# TopLevel.net
KiCad netlist of a schematic drawn in Altium Designer
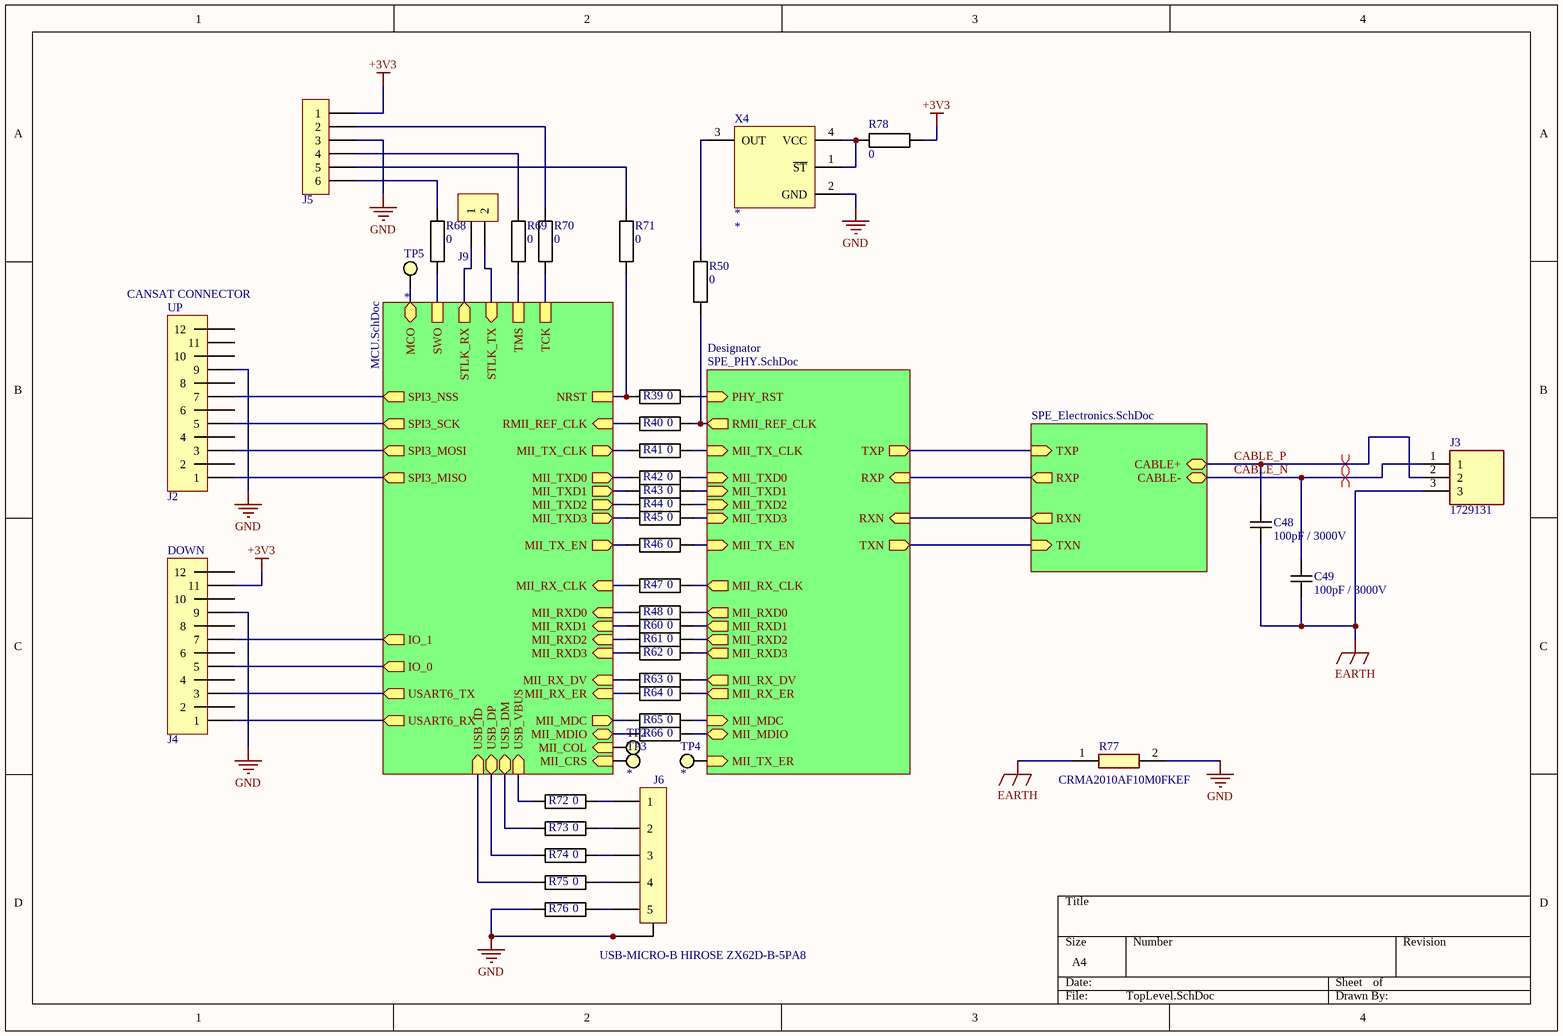
[diagram p0: TopLevel.SchDoc]

(export (version "E")
  (design (tool "Eeschema 10.0.6"))
  (components
    (comp (ref "C48")
      (value "100pF / 3000V")
      (footprint "CAPACITOR 4520 REFLOW")
      (description "Capacitor")
      (libsource (lib "Capacitor") (part "Capacitor"))
    )
    (comp (ref "C49")
      (value "100pF / 3000V")
      (footprint "CAPACITOR 4520 REFLOW")
      (description "Capacitor")
      (libsource (lib "Capacitor") (part "Capacitor"))
    )
    (comp (ref "J2")
      (value "*")
      (footprint "PINHEADER2X6 P2.54 SIDE MOUNT")
      (description "Plug connector")
      (libsource (lib "PinHeader") (part "PinHeader2x6"))
    )
    (comp (ref "J3")
      (value "1729131")
      (footprint "1729131")
      (description "Connector")
      (fields (field (name "MOUSER PART NUMBER") "651-1729131"))
      (libsource (lib "*") (part "1729131"))
    )
    (comp (ref "J4")
      (value "*")
      (footprint "PINHEADER2X6 P2.54 SIDE MOUNT")
      (description "Plug connector")
      (libsource (lib "PinHeader") (part "PinHeader2x6"))
    )
    (comp (ref "J5")
      (value "*")
      (footprint "PinHeader1x6 P2.54")
      (description "Plug connector")
      (libsource (lib "PinHeader") (part "PinHeader1x6"))
    )
    (comp (ref "J6")
      (value "USB-MICRO-B HIROSE ZX62D-B-5PA8")
      (footprint "USB-MICRO-B HIROSE ZX62D-B-5PA8")
      (libsource (lib "Connector") (part "USB-MICRO-B HIROSE ZX62D-B-5PA8"))
    )
    (comp (ref "J9")
      (value "*")
      (footprint "PinHeader1x2 P2.54")
      (description "Plug connector")
      (libsource (lib "PinHeader") (part "PinHeader1x2"))
    )
    (comp (ref "R39")
      (value "0")
      (footprint "RESISTOR 1608 REFLOW")
      (description "Resistor")
      (libsource (lib "Resistor") (part "Resistor"))
    )
    (comp (ref "R40")
      (value "0")
      (footprint "RESISTOR 1608 REFLOW")
      (description "Resistor")
      (libsource (lib "Resistor") (part "Resistor"))
    )
    (comp (ref "R41")
      (value "0")
      (footprint "RESISTOR 1608 REFLOW")
      (description "Resistor")
      (libsource (lib "Resistor") (part "Resistor"))
    )
    (comp (ref "R42")
      (value "0")
      (footprint "RESISTOR 1608 REFLOW")
      (description "Resistor")
      (libsource (lib "Resistor") (part "Resistor"))
    )
    (comp (ref "R43")
      (value "0")
      (footprint "RESISTOR 1608 REFLOW")
      (description "Resistor")
      (libsource (lib "Resistor") (part "Resistor"))
    )
    (comp (ref "R44")
      (value "0")
      (footprint "RESISTOR 1608 REFLOW")
      (description "Resistor")
      (libsource (lib "Resistor") (part "Resistor"))
    )
    (comp (ref "R45")
      (value "0")
      (footprint "RESISTOR 1608 REFLOW")
      (description "Resistor")
      (libsource (lib "Resistor") (part "Resistor"))
    )
    (comp (ref "R46")
      (value "0")
      (footprint "RESISTOR 1608 REFLOW")
      (description "Resistor")
      (libsource (lib "Resistor") (part "Resistor"))
    )
    (comp (ref "R47")
      (value "0")
      (footprint "RESISTOR 1608 REFLOW")
      (description "Resistor")
      (libsource (lib "Resistor") (part "Resistor"))
    )
    (comp (ref "R48")
      (value "0")
      (footprint "RESISTOR 1608 REFLOW")
      (description "Resistor")
      (libsource (lib "Resistor") (part "Resistor"))
    )
    (comp (ref "R50")
      (value "0")
      (footprint "RESISTOR 1608 REFLOW")
      (description "Resistor")
      (libsource (lib "Resistor") (part "Resistor"))
    )
    (comp (ref "R60")
      (value "0")
      (footprint "RESISTOR 1608 REFLOW")
      (description "Resistor")
      (libsource (lib "Resistor") (part "Resistor"))
    )
    (comp (ref "R61")
      (value "0")
      (footprint "RESISTOR 1608 REFLOW")
      (description "Resistor")
      (libsource (lib "Resistor") (part "Resistor"))
    )
    (comp (ref "R62")
      (value "0")
      (footprint "RESISTOR 1608 REFLOW")
      (description "Resistor")
      (libsource (lib "Resistor") (part "Resistor"))
    )
    (comp (ref "R63")
      (value "0")
      (footprint "RESISTOR 1608 REFLOW")
      (description "Resistor")
      (libsource (lib "Resistor") (part "Resistor"))
    )
    (comp (ref "R64")
      (value "0")
      (footprint "RESISTOR 1608 REFLOW")
      (description "Resistor")
      (libsource (lib "Resistor") (part "Resistor"))
    )
    (comp (ref "R65")
      (value "0")
      (footprint "RESISTOR 1608 REFLOW")
      (description "Resistor")
      (libsource (lib "Resistor") (part "Resistor"))
    )
    (comp (ref "R66")
      (value "0")
      (footprint "RESISTOR 1608 REFLOW")
      (description "Resistor")
      (libsource (lib "Resistor") (part "Resistor"))
    )
    (comp (ref "R68")
      (value "0")
      (footprint "RESISTOR 1608 REFLOW")
      (description "Resistor")
      (libsource (lib "Resistor") (part "Resistor"))
    )
    (comp (ref "R69")
      (value "0")
      (footprint "RESISTOR 1608 REFLOW")
      (description "Resistor")
      (libsource (lib "Resistor") (part "Resistor"))
    )
    (comp (ref "R70")
      (value "0")
      (footprint "RESISTOR 1608 REFLOW")
      (description "Resistor")
      (libsource (lib "Resistor") (part "Resistor"))
    )
    (comp (ref "R71")
      (value "0")
      (footprint "RESISTOR 1608 REFLOW")
      (description "Resistor")
      (libsource (lib "Resistor") (part "Resistor"))
    )
    (comp (ref "R72")
      (value "0")
      (footprint "RESISTOR 1005 REFLOW")
      (description "Resistor")
      (libsource (lib "Resistor") (part "Resistor"))
    )
    (comp (ref "R73")
      (value "0")
      (footprint "RESISTOR 1005 REFLOW")
      (description "Resistor")
      (libsource (lib "Resistor") (part "Resistor"))
    )
    (comp (ref "R74")
      (value "0")
      (footprint "RESISTOR 1005 REFLOW")
      (description "Resistor")
      (libsource (lib "Resistor") (part "Resistor"))
    )
    (comp (ref "R75")
      (value "0")
      (footprint "RESISTOR 1005 REFLOW")
      (description "Resistor")
      (libsource (lib "Resistor") (part "Resistor"))
    )
    (comp (ref "R76")
      (value "0")
      (footprint "RESISTOR 1005 REFLOW")
      (description "Resistor")
      (libsource (lib "Resistor") (part "Resistor"))
    )
    (comp (ref "R77")
      (value "CRMA2010AF10M0FKEF")
      (footprint "RESC5125X74N")
      (description "Resistor")
      (fields
        (field (name "MANUFACTURER_PART_NUMBER") "CRMA2010AF1K00FKEF")
        (field (name "MOUSER PART NUMBER") "71-CRMA2010AF1K00FKF")
      )
      (libsource (lib "*") (part "CRMA2010AF1K00FKEF"))
    )
    (comp (ref "R78")
      (value "0")
      (footprint "RESISTOR 1608 REFLOW")
      (description "Resistor")
      (libsource (lib "Resistor") (part "Resistor"))
    )
    (comp (ref "TP2")
      (value "*")
      (footprint "Pad D0.8")
      (description "Pad")
      (libsource (lib "Testpoint") (part "Pad"))
    )
    (comp (ref "TP3")
      (value "*")
      (footprint "Pad D0.8")
      (description "Pad")
      (libsource (lib "Testpoint") (part "Pad"))
    )
    (comp (ref "TP4")
      (value "*")
      (footprint "Pad D0.8")
      (description "Pad")
      (libsource (lib "Testpoint") (part "Pad"))
    )
    (comp (ref "TP5")
      (value "*")
      (footprint "Pad D0.8")
      (description "Pad")
      (libsource (lib "Testpoint") (part "Pad"))
    )
    (comp (ref "X4")
      (value "*")
      (footprint "Oscillator C2.5x2 Seiko Epson SPXO SG-210STF")
      (description "Oscillator C2.5x2 Seiko Epson SPXO SG-210STF")
      (fields (field (name "ALTIUM_VALUE") "*"))
      (libsource (lib "Oscillator") (part "Oscillator C2.5x2.0 Seiko Epson SPXO SG-210STF"))
    )
  )
  (nets
    (net (code "1") (name "+3V3") (class "Default")
      (node (ref "J4") (pin "11") (pinfunction "11_11") (pintype "passive"))
      (node (ref "J5") (pin "1") (pinfunction "1_1") (pintype "passive"))
      (node (ref "R78") (pin "2") (pinfunction "2_2") (pintype "passive"))
    )
    (net (code "2") (name "/CABLE_N") (class "Default")
      (node (ref "C49") (pin "1") (pinfunction "1_1") (pintype "passive"))
      (node (ref "J3") (pin "1") (pinfunction "1_1") (pintype "passive"))
    )
    (net (code "3") (name "/CABLE_P") (class "Default")
      (node (ref "C48") (pin "1") (pinfunction "1_1") (pintype "passive"))
      (node (ref "J3") (pin "2") (pinfunction "2_2") (pintype "passive"))
    )
    (net (code "4") (name "/IO_0") (class "Default")
      (node (ref "J4") (pin "5") (pinfunction "5_5") (pintype "passive"))
    )
    (net (code "5") (name "/IO_1") (class "Default")
      (node (ref "J4") (pin "7") (pinfunction "7_7") (pintype "passive"))
    )
    (net (code "6") (name "/MCO") (class "Default")
      (node (ref "TP5") (pin "1") (pinfunction "1_1") (pintype "passive"))
    )
    (net (code "7") (name "/MII_COL") (class "Default")
      (node (ref "TP2") (pin "1") (pinfunction "1_1") (pintype "passive"))
    )
    (net (code "8") (name "/MII_CRS") (class "Default")
      (node (ref "TP3") (pin "1") (pinfunction "1_1") (pintype "passive"))
    )
    (net (code "9") (name "/MII_MDC") (class "Default")
      (node (ref "R65") (pin "1") (pinfunction "1_1") (pintype "passive"))
    )
    (net (code "10") (name "/MII_MDC_1") (class "Default")
      (node (ref "R65") (pin "2") (pinfunction "2_2") (pintype "passive"))
    )
    (net (code "11") (name "/MII_MDIO") (class "Default")
      (node (ref "R66") (pin "1") (pinfunction "1_1") (pintype "passive"))
    )
    (net (code "12") (name "/MII_MDIO_1") (class "Default")
      (node (ref "R66") (pin "2") (pinfunction "2_2") (pintype "passive"))
    )
    (net (code "13") (name "/MII_RXD0") (class "Default")
      (node (ref "R48") (pin "1") (pinfunction "1_1") (pintype "passive"))
    )
    (net (code "14") (name "/MII_RXD0_1") (class "Default")
      (node (ref "R48") (pin "2") (pinfunction "2_2") (pintype "passive"))
    )
    (net (code "15") (name "/MII_RXD1") (class "Default")
      (node (ref "R60") (pin "1") (pinfunction "1_1") (pintype "passive"))
    )
    (net (code "16") (name "/MII_RXD1_1") (class "Default")
      (node (ref "R60") (pin "2") (pinfunction "2_2") (pintype "passive"))
    )
    (net (code "17") (name "/MII_RXD2") (class "Default")
      (node (ref "R61") (pin "1") (pinfunction "1_1") (pintype "passive"))
    )
    (net (code "18") (name "/MII_RXD2_1") (class "Default")
      (node (ref "R61") (pin "2") (pinfunction "2_2") (pintype "passive"))
    )
    (net (code "19") (name "/MII_RXD3") (class "Default")
      (node (ref "R62") (pin "1") (pinfunction "1_1") (pintype "passive"))
    )
    (net (code "20") (name "/MII_RXD3_1") (class "Default")
      (node (ref "R62") (pin "2") (pinfunction "2_2") (pintype "passive"))
    )
    (net (code "21") (name "/MII_RX_CLK") (class "Default")
      (node (ref "R47") (pin "1") (pinfunction "1_1") (pintype "passive"))
    )
    (net (code "22") (name "/MII_RX_CLK_1") (class "Default")
      (node (ref "R47") (pin "2") (pinfunction "2_2") (pintype "passive"))
    )
    (net (code "23") (name "/MII_RX_DV") (class "Default")
      (node (ref "R63") (pin "1") (pinfunction "1_1") (pintype "passive"))
    )
    (net (code "24") (name "/MII_RX_DV_1") (class "Default")
      (node (ref "R63") (pin "2") (pinfunction "2_2") (pintype "passive"))
    )
    (net (code "25") (name "/MII_RX_ER") (class "Default")
      (node (ref "R64") (pin "1") (pinfunction "1_1") (pintype "passive"))
    )
    (net (code "26") (name "/MII_RX_ER_1") (class "Default")
      (node (ref "R64") (pin "2") (pinfunction "2_2") (pintype "passive"))
    )
    (net (code "27") (name "/MII_TXD0") (class "Default")
      (node (ref "R42") (pin "1") (pinfunction "1_1") (pintype "passive"))
    )
    (net (code "28") (name "/MII_TXD0_1") (class "Default")
      (node (ref "R42") (pin "2") (pinfunction "2_2") (pintype "passive"))
    )
    (net (code "29") (name "/MII_TXD1") (class "Default")
      (node (ref "R43") (pin "1") (pinfunction "1_1") (pintype "passive"))
    )
    (net (code "30") (name "/MII_TXD1_1") (class "Default")
      (node (ref "R43") (pin "2") (pinfunction "2_2") (pintype "passive"))
    )
    (net (code "31") (name "/MII_TXD2") (class "Default")
      (node (ref "R44") (pin "1") (pinfunction "1_1") (pintype "passive"))
    )
    (net (code "32") (name "/MII_TXD2_1") (class "Default")
      (node (ref "R44") (pin "2") (pinfunction "2_2") (pintype "passive"))
    )
    (net (code "33") (name "/MII_TXD3") (class "Default")
      (node (ref "R45") (pin "1") (pinfunction "1_1") (pintype "passive"))
    )
    (net (code "34") (name "/MII_TXD3_1") (class "Default")
      (node (ref "R45") (pin "2") (pinfunction "2_2") (pintype "passive"))
    )
    (net (code "35") (name "/MII_TX_CLK") (class "Default")
      (node (ref "R41") (pin "1") (pinfunction "1_1") (pintype "passive"))
    )
    (net (code "36") (name "/MII_TX_CLK_1") (class "Default")
      (node (ref "R41") (pin "2") (pinfunction "2_2") (pintype "passive"))
    )
    (net (code "37") (name "/MII_TX_EN") (class "Default")
      (node (ref "R46") (pin "1") (pinfunction "1_1") (pintype "passive"))
    )
    (net (code "38") (name "/MII_TX_EN_1") (class "Default")
      (node (ref "R46") (pin "2") (pinfunction "2_2") (pintype "passive"))
    )
    (net (code "39") (name "/MII_TX_ER") (class "Default")
      (node (ref "TP4") (pin "1") (pinfunction "1_1") (pintype "passive"))
    )
    (net (code "40") (name "/NRST") (class "Default")
      (node (ref "R39") (pin "2") (pinfunction "2_2") (pintype "passive"))
      (node (ref "R71") (pin "2") (pinfunction "2_2") (pintype "passive"))
    )
    (net (code "41") (name "/PHY_RST") (class "Default")
      (node (ref "R39") (pin "1") (pinfunction "1_1") (pintype "passive"))
    )
    (net (code "42") (name "/RMII_REF_CLK") (class "Default")
      (node (ref "R40") (pin "1") (pinfunction "1_1") (pintype "passive"))
      (node (ref "R50") (pin "2") (pinfunction "2_2") (pintype "passive"))
    )
    (net (code "43") (name "/RMII_REF_CLK_1") (class "Default")
      (node (ref "R40") (pin "2") (pinfunction "2_2") (pintype "passive"))
    )
    (net (code "46") (name "/SPI3_MISO") (class "Default")
      (node (ref "J2") (pin "1") (pinfunction "1_1") (pintype "passive"))
    )
    (net (code "47") (name "/SPI3_MOSI") (class "Default")
      (node (ref "J2") (pin "3") (pinfunction "3_3") (pintype "passive"))
    )
    (net (code "48") (name "/SPI3_NSS") (class "Default")
      (node (ref "J2") (pin "7") (pinfunction "7_7") (pintype "passive"))
    )
    (net (code "49") (name "/SPI3_SCK") (class "Default")
      (node (ref "J2") (pin "5") (pinfunction "5_5") (pintype "passive"))
    )
    (net (code "50") (name "/STLK_RX") (class "Default")
      (node (ref "J9") (pin "1") (pinfunction "1_1") (pintype "passive"))
    )
    (net (code "51") (name "/STLK_TX") (class "Default")
      (node (ref "J9") (pin "2") (pinfunction "2_2") (pintype "passive"))
    )
    (net (code "52") (name "/SWO") (class "Default")
      (node (ref "R68") (pin "2") (pinfunction "2_2") (pintype "passive"))
    )
    (net (code "53") (name "/TCK") (class "Default")
      (node (ref "R70") (pin "2") (pinfunction "2_2") (pintype "passive"))
    )
    (net (code "54") (name "/TMS") (class "Default")
      (node (ref "R69") (pin "2") (pinfunction "2_2") (pintype "passive"))
    )
    (net (code "57") (name "/USART6_RX") (class "Default")
      (node (ref "J4") (pin "1") (pinfunction "1_1") (pintype "passive"))
    )
    (net (code "58") (name "/USART6_TX") (class "Default")
      (node (ref "J4") (pin "3") (pinfunction "3_3") (pintype "passive"))
    )
    (net (code "59") (name "/USB_DM") (class "Default")
      (node (ref "R73") (pin "2") (pinfunction "2_2") (pintype "passive"))
    )
    (net (code "60") (name "/USB_DP") (class "Default")
      (node (ref "R74") (pin "2") (pinfunction "2_2") (pintype "passive"))
    )
    (net (code "61") (name "/USB_ID") (class "Default")
      (node (ref "R75") (pin "2") (pinfunction "2_2") (pintype "passive"))
    )
    (net (code "62") (name "/USB_VBUS") (class "Default")
      (node (ref "R72") (pin "2") (pinfunction "2_2") (pintype "passive"))
    )
    (net (code "63") (name "EARTH") (class "Default")
      (node (ref "C48") (pin "2") (pinfunction "2_2") (pintype "passive"))
      (node (ref "C49") (pin "2") (pinfunction "2_2") (pintype "passive"))
      (node (ref "J3") (pin "3") (pinfunction "3_3") (pintype "passive"))
      (node (ref "R77") (pin "1") (pinfunction "1_1") (pintype "passive"))
    )
    (net (code "64") (name "GND") (class "Default")
      (node (ref "J2") (pin "9") (pinfunction "9_9") (pintype "passive"))
      (node (ref "J4") (pin "9") (pinfunction "9_9") (pintype "passive"))
      (node (ref "J5") (pin "3") (pinfunction "3_3") (pintype "passive"))
      (node (ref "J6") (pin "6") (pinfunction "6_6") (pintype "passive"))
      (node (ref "J6") (pin "7") (pinfunction "7_7") (pintype "passive"))
      (node (ref "J6") (pin "8") (pinfunction "8_8") (pintype "passive"))
      (node (ref "J6") (pin "9") (pinfunction "9_9") (pintype "passive"))
      (node (ref "R76") (pin "2") (pinfunction "2_2") (pintype "passive"))
      (node (ref "R77") (pin "2") (pinfunction "2_2") (pintype "passive"))
      (node (ref "X4") (pin "2") (pinfunction "GND_2") (pintype "passive"))
    )
    (net (code "65") (name "Net-(J5-Pad2)") (class "Default")
      (node (ref "J5") (pin "2") (pinfunction "2_2") (pintype "passive"))
      (node (ref "R70") (pin "1") (pinfunction "1_1") (pintype "passive"))
    )
    (net (code "66") (name "Net-(J5-Pad4)") (class "Default")
      (node (ref "J5") (pin "4") (pinfunction "4_4") (pintype "passive"))
      (node (ref "R69") (pin "1") (pinfunction "1_1") (pintype "passive"))
    )
    (net (code "67") (name "Net-(J5-Pad5)") (class "Default")
      (node (ref "J5") (pin "5") (pinfunction "5_5") (pintype "passive"))
      (node (ref "R71") (pin "1") (pinfunction "1_1") (pintype "passive"))
    )
    (net (code "68") (name "Net-(J5-Pad6)") (class "Default")
      (node (ref "J5") (pin "6") (pinfunction "6_6") (pintype "passive"))
      (node (ref "R68") (pin "1") (pinfunction "1_1") (pintype "passive"))
    )
    (net (code "69") (name "Net-(J6-Pad1)") (class "Default")
      (node (ref "J6") (pin "1") (pinfunction "1_1") (pintype "passive"))
      (node (ref "R72") (pin "1") (pinfunction "1_1") (pintype "passive"))
    )
    (net (code "70") (name "Net-(J6-Pad2)") (class "Default")
      (node (ref "J6") (pin "2") (pinfunction "2_2") (pintype "passive"))
      (node (ref "R73") (pin "1") (pinfunction "1_1") (pintype "passive"))
    )
    (net (code "71") (name "Net-(J6-Pad3)") (class "Default")
      (node (ref "J6") (pin "3") (pinfunction "3_3") (pintype "passive"))
      (node (ref "R74") (pin "1") (pinfunction "1_1") (pintype "passive"))
    )
    (net (code "72") (name "Net-(J6-Pad4)") (class "Default")
      (node (ref "J6") (pin "4") (pinfunction "4_4") (pintype "passive"))
      (node (ref "R75") (pin "1") (pinfunction "1_1") (pintype "passive"))
    )
    (net (code "73") (name "Net-(J6-Pad5)") (class "Default")
      (node (ref "J6") (pin "5") (pinfunction "5_5") (pintype "passive"))
      (node (ref "R76") (pin "1") (pinfunction "1_1") (pintype "passive"))
    )
    (net (code "74") (name "Net-(X4-OUT)") (class "Default")
      (node (ref "R50") (pin "1") (pinfunction "1_1") (pintype "passive"))
      (node (ref "X4") (pin "3") (pinfunction "OUT_3") (pintype "passive"))
    )
    (net (code "75") (name "Net-(X4-VCC)") (class "Default")
      (node (ref "R78") (pin "1") (pinfunction "1_1") (pintype "passive"))
      (node (ref "X4") (pin "1") (pinfunction "~{ST}_1") (pintype "passive"))
      (node (ref "X4") (pin "4") (pinfunction "VCC_4") (pintype "passive"))
    )
    (net (code "76") (name "unconnected-(J2-Pad2)") (class "Default")
      (node (ref "J2") (pin "2") (pinfunction "2_2") (pintype "passive"))
    )
    (net (code "77") (name "unconnected-(J2-Pad4)") (class "Default")
      (node (ref "J2") (pin "4") (pinfunction "4_4") (pintype "passive"))
    )
    (net (code "78") (name "unconnected-(J2-Pad6)") (class "Default")
      (node (ref "J2") (pin "6") (pinfunction "6_6") (pintype "passive"))
    )
    (net (code "79") (name "unconnected-(J2-Pad8)") (class "Default")
      (node (ref "J2") (pin "8") (pinfunction "8_8") (pintype "passive"))
    )
    (net (code "80") (name "unconnected-(J2-Pad10)") (class "Default")
      (node (ref "J2") (pin "10") (pinfunction "10_10") (pintype "passive"))
    )
    (net (code "81") (name "unconnected-(J2-Pad11)") (class "Default")
      (node (ref "J2") (pin "11") (pinfunction "11_11") (pintype "passive"))
    )
    (net (code "82") (name "unconnected-(J2-Pad12)") (class "Default")
      (node (ref "J2") (pin "12") (pinfunction "12_12") (pintype "passive"))
    )
    (net (code "83") (name "unconnected-(J4-Pad2)") (class "Default")
      (node (ref "J4") (pin "2") (pinfunction "2_2") (pintype "passive"))
    )
    (net (code "84") (name "unconnected-(J4-Pad4)") (class "Default")
      (node (ref "J4") (pin "4") (pinfunction "4_4") (pintype "passive"))
    )
    (net (code "85") (name "unconnected-(J4-Pad6)") (class "Default")
      (node (ref "J4") (pin "6") (pinfunction "6_6") (pintype "passive"))
    )
    (net (code "86") (name "unconnected-(J4-Pad8)") (class "Default")
      (node (ref "J4") (pin "8") (pinfunction "8_8") (pintype "passive"))
    )
    (net (code "87") (name "unconnected-(J4-Pad10)") (class "Default")
      (node (ref "J4") (pin "10") (pinfunction "10_10") (pintype "passive"))
    )
    (net (code "88") (name "unconnected-(J4-Pad12)") (class "Default")
      (node (ref "J4") (pin "12") (pinfunction "12_12") (pintype "passive"))
    )
  )
)
